# mcu.net
KiCad netlist of a schematic drawn in Altium Designer
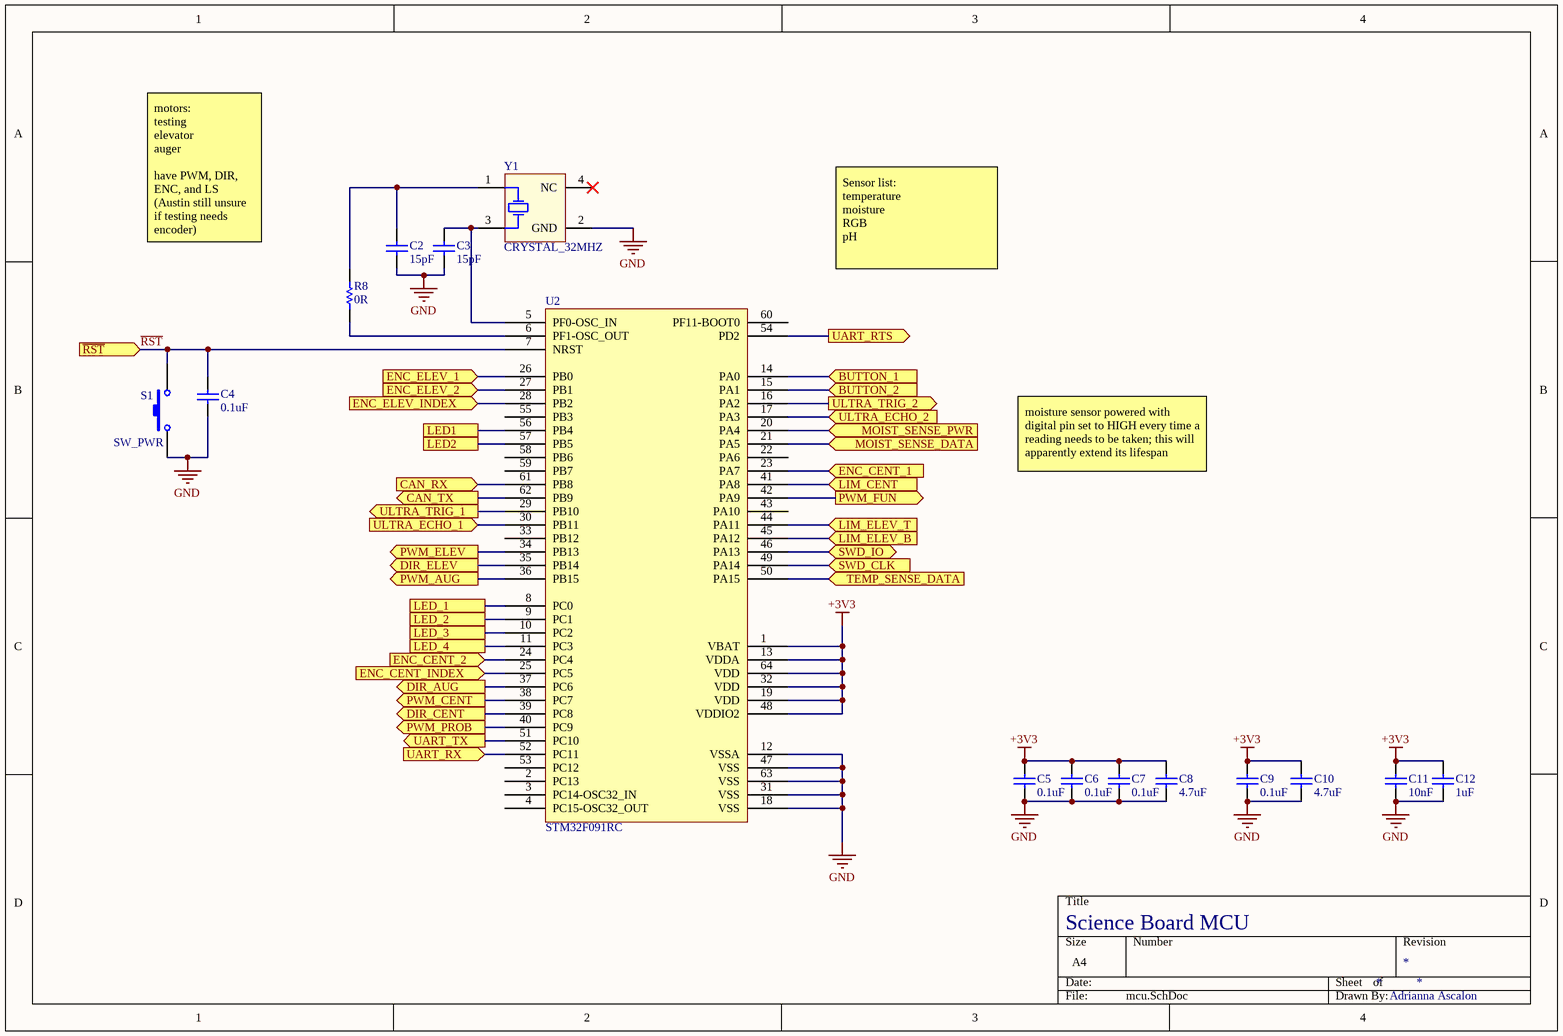
[diagram p0: mcu.SchDoc]

(export (version "E")
  (design (tool "Eeschema 10.0.6"))
  (components
    (comp (ref "C2")
      (value "15pF")
      (footprint "CAPC0603(1608)55_N")
      (description "CAP CER 15PF 250V NPO 0603")
      (fields (field (name "MANUFACTURER") "Yageo") (field (name "MPN") "AC0603JRNPOYBN150"))
      (libsource (lib "UWRT_Schematic_Library_2019") (part "CAP_15pF_0603"))
    )
    (comp (ref "C3")
      (value "15pF")
      (footprint "CAPC0603(1608)55_N")
      (description "CAP CER 15PF 250V NPO 0603")
      (fields (field (name "MANUFACTURER") "Yageo") (field (name "MPN") "AC0603JRNPOYBN150"))
      (libsource (lib "UWRT_Schematic_Library_2019") (part "CAP_15pF_0603"))
    )
    (comp (ref "C4")
      (value "0.1uF")
      (footprint "CAPC0603(1608)55_N")
      (description "CAP CER 0.1UF 16V X7R 0603")
      (fields (field (name "MANUFACTURER") "Yageo") (field (name "MPN") "CC0603KRX7R7BB104"))
      (libsource (lib "UWRT_Schematic_Library_2019") (part "CAP_0.1uF_16V_0603"))
    )
    (comp (ref "C5")
      (value "0.1uF")
      (footprint "CAPC0603(1608)55_N")
      (description "CAP CER 0.1UF 16V X7R 0603")
      (fields (field (name "MANUFACTURER") "Yageo") (field (name "MPN") "CC0603KRX7R7BB104"))
      (libsource (lib "UWRT_Schematic_Library_2019") (part "CAP_0.1uF_16V_0603"))
    )
    (comp (ref "C6")
      (value "0.1uF")
      (footprint "CAPC0603(1608)55_N")
      (description "CAP CER 0.1UF 16V X7R 0603")
      (fields (field (name "MANUFACTURER") "Yageo") (field (name "MPN") "CC0603KRX7R7BB104"))
      (libsource (lib "UWRT_Schematic_Library_2019") (part "CAP_0.1uF_16V_0603"))
    )
    (comp (ref "C7")
      (value "0.1uF")
      (footprint "CAPC0603(1608)55_N")
      (description "CAP CER 0.1UF 16V X7R 0603")
      (fields (field (name "MANUFACTURER") "Yageo") (field (name "MPN") "CC0603KRX7R7BB104"))
      (libsource (lib "UWRT_Schematic_Library_2019") (part "CAP_0.1uF_16V_0603"))
    )
    (comp (ref "C8")
      (value "4.7uF")
      (footprint "CAPC0603(1608)55_N")
      (description "CAP CER 4.7UF 6.3V X5R 0603")
      (fields (field (name "MANUFACTURER") "Yageo") (field (name "MPN") "CC0603KRX5R5BB475"))
      (libsource (lib "UWRT_Schematic_Library_2019") (part "CAP_4.7uF_0603"))
    )
    (comp (ref "C9")
      (value "0.1uF")
      (footprint "CAPC0603(1608)55_N")
      (description "CAP CER 0.1UF 16V X7R 0603")
      (fields (field (name "MANUFACTURER") "Yageo") (field (name "MPN") "CC0603KRX7R7BB104"))
      (libsource (lib "UWRT_Schematic_Library_2019") (part "CAP_0.1uF_16V_0603"))
    )
    (comp (ref "C10")
      (value "4.7uF")
      (footprint "CAPC0603(1608)55_N")
      (description "CAP CER 4.7UF 6.3V X5R 0603")
      (fields (field (name "MANUFACTURER") "Yageo") (field (name "MPN") "CC0603KRX5R5BB475"))
      (libsource (lib "UWRT_Schematic_Library_2019") (part "CAP_4.7uF_0603"))
    )
    (comp (ref "C11")
      (value "10nF")
      (footprint "CAPC0603(1608)55_N")
      (description "CAP CER 10000PF 16V X7R 0603")
      (fields (field (name "MANUFACTURER") "Yageo") (field (name "MPN") "CC0603KRX7R7BB103"))
      (libsource (lib "UWRT_Schematic_Library_2019") (part "CAP_10nF_0603"))
    )
    (comp (ref "C12")
      (value "1uF")
      (footprint "CAPC0603(1608)55_N")
      (description "CAP CER 1UF 16V Y5V 0603")
      (fields (field (name "MANUFACTURER") "Yageo") (field (name "MPN") "CC0603ZRY5V7BB105"))
      (libsource (lib "UWRT_Schematic_Library_2019") (part "CAP_1uF_16V_0603"))
    )
    (comp (ref "R8")
      (value "0R")
      (footprint "RESC0603(1608)_N")
      (description "RES SMD 0 OHM JUMPER 1/10W 0603")
      (fields (field (name "MANUFACTURER") "Yageo") (field (name "MPN") "RC0603JR-070RL"))
      (libsource (lib "UWRT_Schematic_Library_2019") (part "RES_0R_0603"))
    )
    (comp (ref "S1")
      (value "SW_PWR")
      (footprint "PTS830GM140")
      (description "Power Switch (Red)")
      (fields
        (field (name "MPN") "PTS830GM140 SMTR LFS")
        (field (name "DIGIKEY PART NUMBER") "CKN10587CT-ND")
      )
      (libsource (lib "UWRT_Schematic_Library_2019") (part "SW_PWR"))
    )
    (comp (ref "U2")
      (value "STM32F091RC")
      (footprint "UWRT_Footprint_Library_2019:STM_LQFP64_N")
      (fields
        (field (name "MANUFACTURER") "STMicroelectronics")
        (field (name "DIGIKEY PART NUMBER") "497-15167-ND")
      )
      (libsource (lib "UWRT_Schematic_Library_2019") (part "STM32F091RC"))
    )
    (comp (ref "Y1")
      (value "CRYSTAL_32MHZ")
      (footprint "AVX-CX2520DB32000D0GEJZ1-4_V")
      (description "CRYSTAL 32MHZ 8PF SMD")
      (fields
        (field (name "MANUFACTURER") "Kyocera International Inc. Electronic Components")
        (field (name "MPN") "CX2520DB32000D0GPSC1")
      )
      (libsource (lib "UWRT_Schematic_Library_2019") (part "CRYSTAL_32MHZ"))
    )
  )
  (nets
    (net (code "1") (name "+3V3") (class "Default")
      (node (ref "C10") (pin "2") (pinfunction "2_2") (pintype "passive"))
      (node (ref "C11") (pin "2") (pinfunction "2_2") (pintype "passive"))
      (node (ref "C12") (pin "2") (pinfunction "2_2") (pintype "passive"))
      (node (ref "C5") (pin "1") (pinfunction "1_1") (pintype "passive"))
      (node (ref "C6") (pin "1") (pinfunction "1_1") (pintype "passive"))
      (node (ref "C7") (pin "1") (pinfunction "1_1") (pintype "passive"))
      (node (ref "C8") (pin "2") (pinfunction "2_2") (pintype "passive"))
      (node (ref "C9") (pin "1") (pinfunction "1_1") (pintype "passive"))
      (node (ref "U2") (pin "1") (pinfunction "VBAT_1") (pintype "passive"))
      (node (ref "U2") (pin "13") (pinfunction "VDDA_13") (pintype "passive"))
      (node (ref "U2") (pin "19") (pinfunction "VDD_19") (pintype "passive"))
      (node (ref "U2") (pin "32") (pinfunction "VDD_32") (pintype "passive"))
      (node (ref "U2") (pin "48") (pinfunction "VDDIO2_48") (pintype "passive"))
      (node (ref "U2") (pin "64") (pinfunction "VDD_64") (pintype "passive"))
    )
    (net (code "2") (name "/BUTTON_1") (class "Default")
      (node (ref "U2") (pin "14") (pinfunction "PA0_14") (pintype "passive"))
    )
    (net (code "3") (name "/BUTTON_2") (class "Default")
      (node (ref "U2") (pin "15") (pinfunction "PA1_15") (pintype "passive"))
    )
    (net (code "4") (name "/CAN_RX") (class "Default")
      (node (ref "U2") (pin "61") (pinfunction "PB8_61") (pintype "passive"))
    )
    (net (code "5") (name "/CAN_TX") (class "Default")
      (node (ref "U2") (pin "62") (pinfunction "PB9_62") (pintype "passive"))
    )
    (net (code "6") (name "/DIR_AUG") (class "Default")
      (node (ref "U2") (pin "37") (pinfunction "PC6_37") (pintype "passive"))
    )
    (net (code "7") (name "/DIR_CENT") (class "Default")
      (node (ref "U2") (pin "39") (pinfunction "PC8_39") (pintype "passive"))
    )
    (net (code "8") (name "/DIR_ELEV") (class "Default")
      (node (ref "U2") (pin "35") (pinfunction "PB14_35") (pintype "passive"))
    )
    (net (code "9") (name "/ENC_CENT_1") (class "Default")
      (node (ref "U2") (pin "23") (pinfunction "PA7_23") (pintype "passive"))
    )
    (net (code "10") (name "/ENC_CENT_2") (class "Default")
      (node (ref "U2") (pin "24") (pinfunction "PC4_24") (pintype "passive"))
    )
    (net (code "11") (name "/ENC_CENT_INDEX") (class "Default")
      (node (ref "U2") (pin "25") (pinfunction "PC5_25") (pintype "passive"))
    )
    (net (code "12") (name "/ENC_ELEV_1") (class "Default")
      (node (ref "U2") (pin "26") (pinfunction "PB0_26") (pintype "passive"))
    )
    (net (code "13") (name "/ENC_ELEV_2") (class "Default")
      (node (ref "U2") (pin "27") (pinfunction "PB1_27") (pintype "passive"))
    )
    (net (code "14") (name "/ENC_ELEV_INDEX") (class "Default")
      (node (ref "U2") (pin "28") (pinfunction "PB2_28") (pintype "passive"))
    )
    (net (code "15") (name "/LED1") (class "Default")
      (node (ref "U2") (pin "56") (pinfunction "PB4_56") (pintype "passive"))
    )
    (net (code "16") (name "/LED2") (class "Default")
      (node (ref "U2") (pin "57") (pinfunction "PB5_57") (pintype "passive"))
    )
    (net (code "17") (name "/LED_1") (class "Default")
      (node (ref "U2") (pin "8") (pinfunction "PC0_8") (pintype "passive"))
    )
    (net (code "18") (name "/LED_2") (class "Default")
      (node (ref "U2") (pin "9") (pinfunction "PC1_9") (pintype "passive"))
    )
    (net (code "19") (name "/LED_3") (class "Default")
      (node (ref "U2") (pin "10") (pinfunction "PC2_10") (pintype "passive"))
    )
    (net (code "20") (name "/LED_4") (class "Default")
      (node (ref "U2") (pin "11") (pinfunction "PC3_11") (pintype "passive"))
    )
    (net (code "21") (name "/LIM_CENT") (class "Default")
      (node (ref "U2") (pin "41") (pinfunction "PA8_41") (pintype "passive"))
    )
    (net (code "22") (name "/LIM_ELEV_B") (class "Default")
      (node (ref "U2") (pin "45") (pinfunction "PA12_45") (pintype "passive"))
    )
    (net (code "23") (name "/LIM_ELEV_T") (class "Default")
      (node (ref "U2") (pin "44") (pinfunction "PA11_44") (pintype "passive"))
    )
    (net (code "24") (name "/MOIST_SENSE_DATA") (class "Default")
      (node (ref "U2") (pin "21") (pinfunction "PA5_21") (pintype "passive"))
    )
    (net (code "25") (name "/MOIST_SENSE_PWR") (class "Default")
      (node (ref "U2") (pin "20") (pinfunction "PA4_20") (pintype "passive"))
    )
    (net (code "26") (name "/PWM_AUG") (class "Default")
      (node (ref "U2") (pin "36") (pinfunction "PB15_36") (pintype "passive"))
    )
    (net (code "27") (name "/PWM_CENT") (class "Default")
      (node (ref "U2") (pin "38") (pinfunction "PC7_38") (pintype "passive"))
    )
    (net (code "28") (name "/PWM_ELEV") (class "Default")
      (node (ref "U2") (pin "34") (pinfunction "PB13_34") (pintype "passive"))
    )
    (net (code "29") (name "/PWM_FUN") (class "Default")
      (node (ref "U2") (pin "42") (pinfunction "PA9_42") (pintype "passive"))
    )
    (net (code "30") (name "/PWM_PROB") (class "Default")
      (node (ref "U2") (pin "40") (pinfunction "PC9_40") (pintype "passive"))
    )
    (net (code "31") (name "/SWD_CLK") (class "Default")
      (node (ref "U2") (pin "49") (pinfunction "PA14_49") (pintype "passive"))
    )
    (net (code "32") (name "/SWD_IO") (class "Default")
      (node (ref "U2") (pin "46") (pinfunction "PA13_46") (pintype "passive"))
    )
    (net (code "33") (name "/TEMP_SENSE_DATA") (class "Default")
      (node (ref "U2") (pin "50") (pinfunction "PA15_50") (pintype "passive"))
    )
    (net (code "34") (name "/UART_RTS") (class "Default")
      (node (ref "U2") (pin "54") (pinfunction "PD2_54") (pintype "passive"))
    )
    (net (code "35") (name "/UART_RX") (class "Default")
      (node (ref "U2") (pin "52") (pinfunction "PC11_52") (pintype "passive"))
    )
    (net (code "36") (name "/UART_TX") (class "Default")
      (node (ref "U2") (pin "51") (pinfunction "PC10_51") (pintype "passive"))
    )
    (net (code "37") (name "/ULTRA_ECHO_1") (class "Default")
      (node (ref "U2") (pin "30") (pinfunction "PB11_30") (pintype "passive"))
    )
    (net (code "38") (name "/ULTRA_ECHO_2") (class "Default")
      (node (ref "U2") (pin "17") (pinfunction "PA3_17") (pintype "passive"))
    )
    (net (code "39") (name "/ULTRA_TRIG_1") (class "Default")
      (node (ref "U2") (pin "29") (pinfunction "PB10_29") (pintype "passive"))
    )
    (net (code "40") (name "/ULTRA_TRIG_2") (class "Default")
      (node (ref "U2") (pin "16") (pinfunction "PA2_16") (pintype "passive"))
    )
    (net (code "41") (name "/~{RST}") (class "Default")
      (node (ref "C4") (pin "2") (pinfunction "2_2") (pintype "passive"))
      (node (ref "S1") (pin "2") (pinfunction "2_2") (pintype "passive"))
      (node (ref "U2") (pin "7") (pinfunction "NRST_7") (pintype "passive"))
    )
    (net (code "42") (name "GND") (class "Default")
      (node (ref "C10") (pin "1") (pinfunction "1_1") (pintype "passive"))
      (node (ref "C11") (pin "1") (pinfunction "1_1") (pintype "passive"))
      (node (ref "C12") (pin "1") (pinfunction "1_1") (pintype "passive"))
      (node (ref "C2") (pin "1") (pinfunction "1_1") (pintype "passive"))
      (node (ref "C3") (pin "1") (pinfunction "1_1") (pintype "passive"))
      (node (ref "C4") (pin "1") (pinfunction "1_1") (pintype "passive"))
      (node (ref "C5") (pin "2") (pinfunction "2_2") (pintype "passive"))
      (node (ref "C6") (pin "2") (pinfunction "2_2") (pintype "passive"))
      (node (ref "C7") (pin "2") (pinfunction "2_2") (pintype "passive"))
      (node (ref "C8") (pin "1") (pinfunction "1_1") (pintype "passive"))
      (node (ref "C9") (pin "2") (pinfunction "2_2") (pintype "passive"))
      (node (ref "S1") (pin "1") (pinfunction "1_1") (pintype "passive"))
      (node (ref "U2") (pin "12") (pinfunction "VSSA_12") (pintype "passive"))
      (node (ref "U2") (pin "18") (pinfunction "VSS_18") (pintype "passive"))
      (node (ref "U2") (pin "31") (pinfunction "VSS_31") (pintype "passive"))
      (node (ref "U2") (pin "47") (pinfunction "VSS_47") (pintype "passive"))
      (node (ref "U2") (pin "63") (pinfunction "VSS_63") (pintype "passive"))
      (node (ref "Y1") (pin "2") (pinfunction "GND_2") (pintype "power_in"))
    )
    (net (code "43") (name "Net-(C2-Pad2)") (class "Default")
      (node (ref "C2") (pin "2") (pinfunction "2_2") (pintype "passive"))
      (node (ref "R8") (pin "2") (pinfunction "2_2") (pintype "passive"))
      (node (ref "Y1") (pin "1") (pinfunction "HOT_1") (pintype "passive"))
    )
    (net (code "44") (name "Net-(U2-PF0-OSC_IN)") (class "Default")
      (node (ref "C3") (pin "2") (pinfunction "2_2") (pintype "passive"))
      (node (ref "U2") (pin "5") (pinfunction "PF0-OSC_IN_5") (pintype "passive"))
      (node (ref "Y1") (pin "3") (pinfunction "HOT_3") (pintype "passive"))
    )
    (net (code "45") (name "Net-(U2-PF1-OSC_OUT)") (class "Default")
      (node (ref "R8") (pin "1") (pinfunction "1_1") (pintype "passive"))
      (node (ref "U2") (pin "6") (pinfunction "PF1-OSC_OUT_6") (pintype "passive"))
    )
    (net (code "46") (name "unconnected-(U2-PA6-Pad22)") (class "Default")
      (node (ref "U2") (pin "22") (pinfunction "PA6_22") (pintype "passive"))
    )
    (net (code "47") (name "unconnected-(U2-PA10-Pad43)") (class "Default")
      (node (ref "U2") (pin "43") (pinfunction "PA10_43") (pintype "passive"))
    )
    (net (code "48") (name "unconnected-(U2-PB3-Pad55)") (class "Default")
      (node (ref "U2") (pin "55") (pinfunction "PB3_55") (pintype "passive"))
    )
    (net (code "49") (name "unconnected-(U2-PB6-Pad58)") (class "Default")
      (node (ref "U2") (pin "58") (pinfunction "PB6_58") (pintype "passive"))
    )
    (net (code "50") (name "unconnected-(U2-PB7-Pad59)") (class "Default")
      (node (ref "U2") (pin "59") (pinfunction "PB7_59") (pintype "passive"))
    )
    (net (code "51") (name "unconnected-(U2-PB12-Pad33)") (class "Default")
      (node (ref "U2") (pin "33") (pinfunction "PB12_33") (pintype "passive"))
    )
    (net (code "52") (name "unconnected-(U2-PC12-Pad53)") (class "Default")
      (node (ref "U2") (pin "53") (pinfunction "PC12_53") (pintype "passive"))
    )
    (net (code "53") (name "unconnected-(U2-PC13-Pad2)") (class "Default")
      (node (ref "U2") (pin "2") (pinfunction "PC13_2") (pintype "passive"))
    )
    (net (code "54") (name "unconnected-(U2-PC14-OSC32_IN-Pad3)") (class "Default")
      (node (ref "U2") (pin "3") (pinfunction "PC14-OSC32_IN_3") (pintype "passive"))
    )
    (net (code "55") (name "unconnected-(U2-PC15-OSC32_OUT-Pad4)") (class "Default")
      (node (ref "U2") (pin "4") (pinfunction "PC15-OSC32_OUT_4") (pintype "passive"))
    )
    (net (code "56") (name "unconnected-(U2-PF11-BOOT0-Pad60)") (class "Default")
      (node (ref "U2") (pin "60") (pinfunction "PF11-BOOT0_60") (pintype "passive"))
    )
    (net (code "57") (name "unconnected-(Y1-NC-Pad4)") (class "Default")
      (node (ref "Y1") (pin "4") (pinfunction "NC_4") (pintype "passive+no_connect"))
    )
  )
)
